# 0HP_Vactrol_LPG-VCA_REV_1.net
KiCad netlist of a schematic drawn in EAGLE
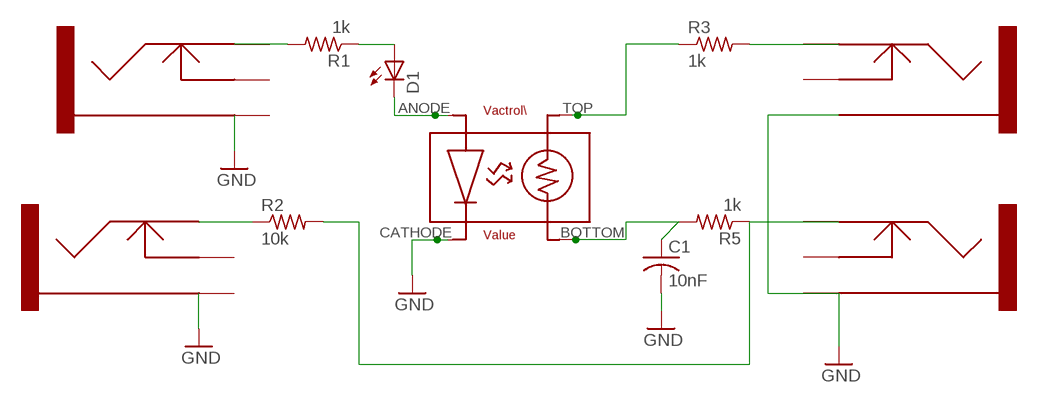
[diagram p0: schematic, sheet 1]

(export (version "E")
  (design (tool "Eeschema 10.0.6"))
  (components
    (comp (ref "C1")
      (value "10nF")
      (footprint "eagle-import:C025-024X044")
      (libsource (lib "eagle-import") (part "C-US025-024X044"))
    )
    (comp (ref "CV1")
      (value "3.5MMJACK")
      (footprint "eagle-import:3.5MMPHONEJACK")
      (libsource (lib "eagle-import") (part "3.5MMJACK"))
    )
    (comp (ref "CV2")
      (value "3.5MMJACK")
      (footprint "eagle-import:3.5MMPHONEJACK")
      (libsource (lib "eagle-import") (part "3.5MMJACK"))
    )
    (comp (ref "D1")
      (value "LED3MM")
      (footprint "eagle-import:LED3MM")
      (libsource (lib "eagle-import") (part "LED3MM"))
    )
    (comp (ref "IN")
      (value "3.5MMJACK")
      (footprint "eagle-import:3.5MMPHONEJACK")
      (libsource (lib "eagle-import") (part "3.5MMJACK"))
    )
    (comp (ref "OUT")
      (value "3.5MMJACK")
      (footprint "eagle-import:3.5MMPHONEJACK")
      (libsource (lib "eagle-import") (part "3.5MMJACK"))
    )
    (comp (ref "R1")
      (value "1k")
      (footprint "eagle-import:0207_2V")
      (libsource (lib "eagle-import") (part "R-US_0207/2V"))
    )
    (comp (ref "R2")
      (value "10k")
      (footprint "eagle-import:0207_2V")
      (libsource (lib "eagle-import") (part "R-US_0207/2V"))
    )
    (comp (ref "R3")
      (value "1k")
      (footprint "eagle-import:0207_2V")
      (libsource (lib "eagle-import") (part "R-US_0207/2V"))
    )
    (comp (ref "R5")
      (value "1k")
      (footprint "eagle-import:0207_2V")
      (libsource (lib "eagle-import") (part "R-US_0207/2V"))
    )
    (comp (ref "U$1")
      (value "VACTROL")
      (footprint "eagle-import:VACTROL")
      (libsource (lib "eagle-import") (part "VACTROL"))
    )
  )
  (nets
    (net (code "1") (name "GND") (class "Default")
      (node (ref "C1") (pin "2") (pinfunction "2_2") (pintype "passive"))
      (node (ref "CV1") (pin "SLEEVE") (pinfunction "SLEEVE_SLEEVE") (pintype "bidirectional"))
      (node (ref "CV2") (pin "SLEEVE") (pinfunction "SLEEVE_SLEEVE") (pintype "bidirectional"))
      (node (ref "IN") (pin "SLEEVE") (pinfunction "SLEEVE_SLEEVE") (pintype "bidirectional"))
      (node (ref "OUT") (pin "SLEEVE") (pinfunction "SLEEVE_SLEEVE") (pintype "bidirectional"))
      (node (ref "U$1") (pin "CATHODE") (pinfunction "CATHODE_CATHODE") (pintype "bidirectional"))
    )
    (net (code "2") (name "Net-(C1-Pad1)") (class "Default")
      (node (ref "C1") (pin "1") (pinfunction "1_1") (pintype "passive"))
      (node (ref "R5") (pin "2") (pinfunction "2_2") (pintype "passive"))
      (node (ref "U$1") (pin "BOTTOM") (pinfunction "BOTTOM_BOTTOM") (pintype "bidirectional"))
    )
    (net (code "3") (name "Net-(CV1-PadTIP)") (class "Default")
      (node (ref "CV1") (pin "TIP") (pinfunction "TIP_TIP") (pintype "bidirectional"))
      (node (ref "R2") (pin "1") (pinfunction "1_1") (pintype "passive"))
    )
    (net (code "4") (name "Net-(CV2-PadTIP)") (class "Default")
      (node (ref "CV2") (pin "TIP") (pinfunction "TIP_TIP") (pintype "bidirectional"))
      (node (ref "R1") (pin "2") (pinfunction "2_2") (pintype "passive"))
    )
    (net (code "5") (name "Net-(D1-C)") (class "Default")
      (node (ref "D1") (pin "K") (pinfunction "C_K") (pintype "passive"))
      (node (ref "U$1") (pin "ANODE") (pinfunction "ANODE_ANODE") (pintype "bidirectional"))
    )
    (net (code "6") (name "Net-(D1-PadA)") (class "Default")
      (node (ref "D1") (pin "A") (pinfunction "A_A") (pintype "passive"))
      (node (ref "R1") (pin "1") (pinfunction "1_1") (pintype "passive"))
    )
    (net (code "7") (name "Net-(IN-PadTIP)") (class "Default")
      (node (ref "IN") (pin "TIP") (pinfunction "TIP_TIP") (pintype "bidirectional"))
      (node (ref "R2") (pin "2") (pinfunction "2_2") (pintype "passive"))
      (node (ref "R5") (pin "1") (pinfunction "1_1") (pintype "passive"))
    )
    (net (code "8") (name "Net-(OUT-PadTIP)") (class "Default")
      (node (ref "OUT") (pin "TIP") (pinfunction "TIP_TIP") (pintype "bidirectional"))
      (node (ref "R3") (pin "2") (pinfunction "2_2") (pintype "passive"))
    )
    (net (code "9") (name "Net-(R3-Pad1)") (class "Default")
      (node (ref "R3") (pin "1") (pinfunction "1_1") (pintype "passive"))
      (node (ref "U$1") (pin "TOP") (pinfunction "TOP_TOP") (pintype "bidirectional"))
    )
    (net (code "10") (name "unconnected-(CV1-PadSWITCH)") (class "Default")
      (node (ref "CV1") (pin "SWITCH") (pinfunction "SWITCH_SWITCH") (pintype "bidirectional"))
    )
    (net (code "11") (name "unconnected-(CV2-PadSWITCH)") (class "Default")
      (node (ref "CV2") (pin "SWITCH") (pinfunction "SWITCH_SWITCH") (pintype "bidirectional"))
    )
    (net (code "12") (name "unconnected-(IN-PadSWITCH)") (class "Default")
      (node (ref "IN") (pin "SWITCH") (pinfunction "SWITCH_SWITCH") (pintype "bidirectional"))
    )
    (net (code "13") (name "unconnected-(OUT-PadSWITCH)") (class "Default")
      (node (ref "OUT") (pin "SWITCH") (pinfunction "SWITCH_SWITCH") (pintype "bidirectional"))
    )
  )
)
